# Arduino-Teensy-v5_PLUS_ESP-12E_4LAYER.net
KiCad netlist of a schematic drawn in EAGLE
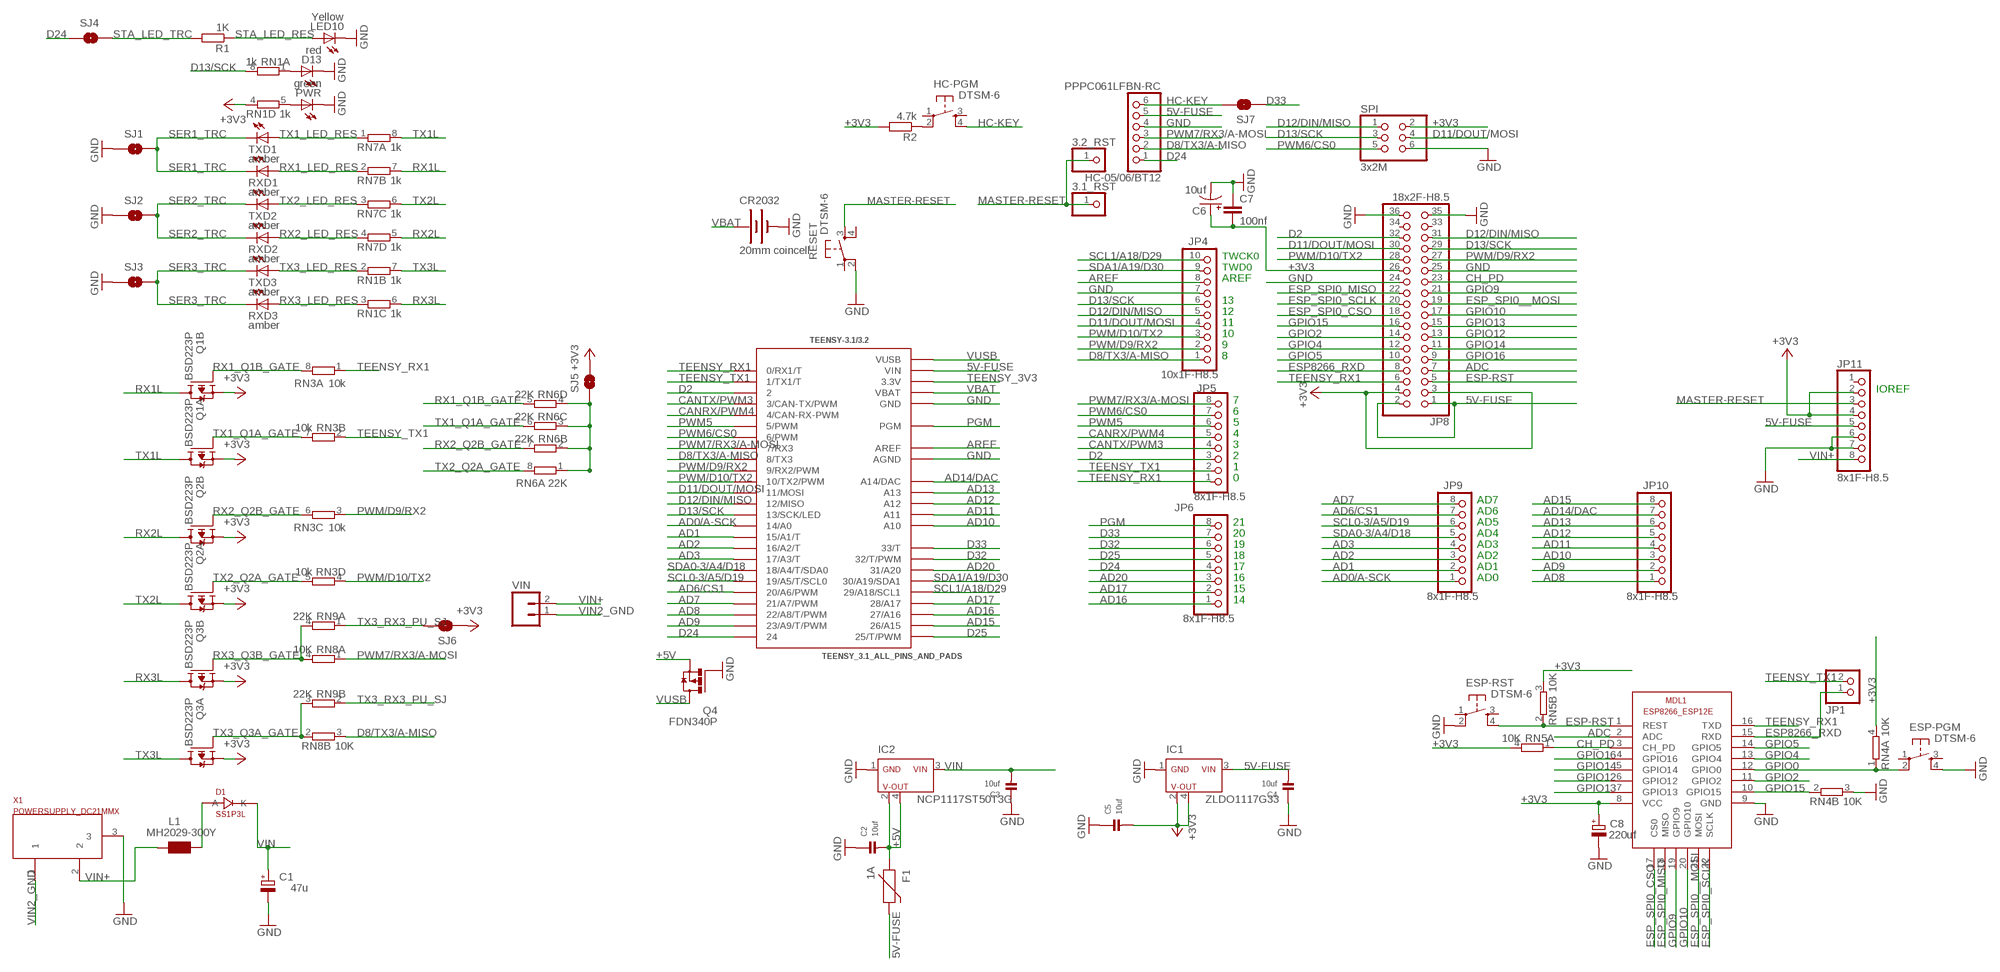
[diagram p0: schematic, sheet 1]

(export (version "E")
  (design (tool "Eeschema 10.0.6"))
  (components
    (comp (ref "3.1_RST")
      (value "PINHD-1X1CB")
      (footprint "eagle-import:1X01-CLEANBIG")
      (libsource (lib "eagle-import") (part "PINHD-1X1CB"))
    )
    (comp (ref "3.2_RST")
      (value "PINHD-1X1CB")
      (footprint "eagle-import:1X01-CLEANBIG")
      (libsource (lib "eagle-import") (part "PINHD-1X1CB"))
    )
    (comp (ref "C1")
      (value "47u")
      (footprint "eagle-import:PANASONIC_D")
      (libsource (lib "eagle-import") (part "CPOL-EUD"))
    )
    (comp (ref "C2")
      (value "10uf")
      (footprint "eagle-import:0805")
      (libsource (lib "eagle-import") (part "CAP_CERAMIC0805"))
    )
    (comp (ref "C3")
      (value "10uf")
      (footprint "eagle-import:0805")
      (libsource (lib "eagle-import") (part "CAP_CERAMIC0805"))
    )
    (comp (ref "C4")
      (value "10uf")
      (footprint "eagle-import:0805")
      (libsource (lib "eagle-import") (part "CAP_CERAMIC0805"))
    )
    (comp (ref "C5")
      (value "10uf")
      (footprint "eagle-import:0805")
      (libsource (lib "eagle-import") (part "CAP_CERAMIC0805"))
    )
    (comp (ref "C6")
      (value "10uf")
      (footprint "eagle-import:A_3216-18R")
      (libsource (lib "eagle-import") (part "CPOL-USA/3216-18R"))
    )
    (comp (ref "C7")
      (value "100nf")
      (footprint "eagle-import:C0603-ROUND")
      (libsource (lib "eagle-import") (part "C-EUC0603"))
    )
    (comp (ref "C8")
      (value "220uf")
      (footprint "eagle-import:SMC_B")
      (libsource (lib "eagle-import") (part "CPOL-EUSMCB"))
    )
    (comp (ref "CR2032")
      (value "20mm coincell")
      (footprint "eagle-import:BATTCON_20MM_4LEGS")
      (libsource (lib "eagle-import") (part "BATTERY20MM_4LEGS"))
    )
    (comp (ref "D1")
      (value "SS1P3L")
      (footprint "eagle-import:DO220AAL")
      (libsource (lib "eagle-import") (part "SS1P3L"))
    )
    (comp (ref "D13")
      (value "red")
      (footprint "eagle-import:CHIPLED_0805")
      (libsource (lib "eagle-import") (part "LEDCHIPLED_0805"))
    )
    (comp (ref "ESP-PGM")
      (value "DTSM-6")
      (footprint "eagle-import:DTSM-6")
      (libsource (lib "eagle-import") (part "DTSM-6"))
    )
    (comp (ref "ESP-RST")
      (value "DTSM-6")
      (footprint "eagle-import:DTSM-6")
      (libsource (lib "eagle-import") (part "DTSM-6"))
    )
    (comp (ref "F1")
      (value "1A")
      (footprint "eagle-import:PTC-1206")
      (libsource (lib "eagle-import") (part "PTCSMD"))
    )
    (comp (ref "HC-05/06/BT12")
      (value "PPPC061LFBN-RC")
      (footprint "eagle-import:1X06")
      (libsource (lib "eagle-import") (part "PINHD-1X6"))
    )
    (comp (ref "HC-PGM")
      (value "DTSM-6")
      (footprint "eagle-import:DTSM-6")
      (libsource (lib "eagle-import") (part "DTSM-6"))
    )
    (comp (ref "IC1")
      (value "ZLDO1117G33")
      (footprint "eagle-import:SOT223")
      (libsource (lib "eagle-import") (part "ZLDO1117G33"))
    )
    (comp (ref "IC2")
      (value "NCP1117ST50T3G")
      (footprint "eagle-import:SOT223")
      (libsource (lib "eagle-import") (part "NCP1117ST50T3G"))
    )
    (comp (ref "JP1")
      (value "PINHD-1X2")
      (footprint "eagle-import:1X02")
      (libsource (lib "eagle-import") (part "PINHD-1X2"))
    )
    (comp (ref "JP4")
      (value "10x1F-H8.5")
      (footprint "eagle-import:1X10")
      (libsource (lib "eagle-import") (part "PINHD-1X10"))
    )
    (comp (ref "JP5")
      (value "8x1F-H8.5")
      (footprint "eagle-import:1X08")
      (libsource (lib "eagle-import") (part "PINHD-1X8"))
    )
    (comp (ref "JP6")
      (value "8x1F-H8.5")
      (footprint "eagle-import:1X08")
      (libsource (lib "eagle-import") (part "PINHD-1X8"))
    )
    (comp (ref "JP8")
      (value "18x2F-H8.5")
      (footprint "eagle-import:2X18")
      (libsource (lib "eagle-import") (part "PINHD-2X18"))
    )
    (comp (ref "JP9")
      (value "8x1F-H8.5")
      (footprint "eagle-import:1X08")
      (libsource (lib "eagle-import") (part "PINHD-1X8"))
    )
    (comp (ref "JP10")
      (value "8x1F-H8.5")
      (footprint "eagle-import:1X08")
      (libsource (lib "eagle-import") (part "PINHD-1X8"))
    )
    (comp (ref "JP11")
      (value "8x1F-H8.5")
      (footprint "eagle-import:1X08")
      (libsource (lib "eagle-import") (part "PINHD-1X8"))
    )
    (comp (ref "L1")
      (value "MH2029-300Y")
      (footprint "eagle-import:0805")
      (libsource (lib "eagle-import") (part "WE-CBF_0805"))
    )
    (comp (ref "LED10")
      (value "Yellow")
      (footprint "eagle-import:CHIPLED_0805")
      (libsource (lib "eagle-import") (part "LEDCHIPLED_0805"))
    )
    (comp (ref "MDL1")
      (value "ESP8266-12E)")
      (footprint "eagle-import:ESP8266-ESP12E")
      (libsource (lib "eagle-import") (part "ESP8266-12EESP8266-ESP12E"))
    )
    (comp (ref "PWR")
      (value "green")
      (footprint "eagle-import:CHIPLED_0805")
      (libsource (lib "eagle-import") (part "LEDCHIPLED_0805"))
    )
    (comp (ref "Q1")
      (value "BSD223P")
      (footprint "eagle-import:SOT363_INFINEON")
      (libsource (lib "eagle-import") (part "BSD223P"))
    )
    (comp (ref "Q2")
      (value "BSD223P")
      (footprint "eagle-import:SOT363_INFINEON")
      (libsource (lib "eagle-import") (part "BSD223P"))
    )
    (comp (ref "Q3")
      (value "BSD223P")
      (footprint "eagle-import:SOT363_INFINEON")
      (libsource (lib "eagle-import") (part "BSD223P"))
    )
    (comp (ref "Q4")
      (value "FDN340P")
      (footprint "eagle-import:SUPER-SOT3")
      (libsource (lib "eagle-import") (part "FDN360P"))
    )
    (comp (ref "R1")
      (value "1K")
      (footprint "eagle-import:R0603")
      (libsource (lib "eagle-import") (part "R-EU_R0603"))
    )
    (comp (ref "R2")
      (value "4.7k")
      (footprint "eagle-import:R0603")
      (libsource (lib "eagle-import") (part "R-EU_R0603"))
    )
    (comp (ref "RESET")
      (value "DTSM-6")
      (footprint "eagle-import:DTSM-6")
      (libsource (lib "eagle-import") (part "DTSM-6"))
    )
    (comp (ref "RN1")
      (value "1k")
      (footprint "eagle-import:CAT16")
      (libsource (lib "eagle-import") (part "4R-NCAT16"))
    )
    (comp (ref "RN3")
      (value "10k")
      (footprint "eagle-import:CAT16")
      (libsource (lib "eagle-import") (part "4R-NCAT16"))
    )
    (comp (ref "RN4")
      (value "10K")
      (footprint "eagle-import:EXB34V")
      (libsource (lib "eagle-import") (part "2R-NEXB34V"))
    )
    (comp (ref "RN5")
      (value "10K")
      (footprint "eagle-import:EXB34V")
      (libsource (lib "eagle-import") (part "2R-NEXB34V"))
    )
    (comp (ref "RN6")
      (value "22K")
      (footprint "eagle-import:CAT16")
      (libsource (lib "eagle-import") (part "4R-NCAT16"))
    )
    (comp (ref "RN7")
      (value "1k")
      (footprint "eagle-import:CAT16")
      (libsource (lib "eagle-import") (part "4R-NCAT16"))
    )
    (comp (ref "RN8")
      (value "10K")
      (footprint "eagle-import:EXB34V")
      (libsource (lib "eagle-import") (part "2R-NEXB34V"))
    )
    (comp (ref "RN9")
      (value "22K")
      (footprint "eagle-import:EXB34V")
      (libsource (lib "eagle-import") (part "2R-NEXB34V"))
    )
    (comp (ref "RXD1")
      (value "amber")
      (footprint "eagle-import:CHIPLED_0805")
      (libsource (lib "eagle-import") (part "LEDCHIPLED_0805"))
    )
    (comp (ref "RXD2")
      (value "amber")
      (footprint "eagle-import:CHIPLED_0805")
      (libsource (lib "eagle-import") (part "LEDCHIPLED_0805"))
    )
    (comp (ref "RXD3")
      (value "amber")
      (footprint "eagle-import:CHIPLED_0805")
      (libsource (lib "eagle-import") (part "LEDCHIPLED_0805"))
    )
    (comp (ref "SJ1")
      (value "SOLDERJUMPERTRACE")
      (footprint "eagle-import:SJ_2S-TRACE")
      (libsource (lib "eagle-import") (part "SOLDERJUMPERTRACE"))
    )
    (comp (ref "SJ2")
      (value "SOLDERJUMPERTRACE")
      (footprint "eagle-import:SJ_2S-TRACE")
      (libsource (lib "eagle-import") (part "SOLDERJUMPERTRACE"))
    )
    (comp (ref "SJ3")
      (value "SOLDERJUMPERTRACE")
      (footprint "eagle-import:SJ_2S-TRACE")
      (libsource (lib "eagle-import") (part "SOLDERJUMPERTRACE"))
    )
    (comp (ref "SJ4")
      (value "SOLDERJUMPERTRACE")
      (footprint "eagle-import:SJ_2S-TRACE")
      (libsource (lib "eagle-import") (part "SOLDERJUMPERTRACE"))
    )
    (comp (ref "SJ5")
      (value "SOLDERJUMPERTRACE")
      (footprint "eagle-import:SJ_2S-TRACE")
      (libsource (lib "eagle-import") (part "SOLDERJUMPERTRACE"))
    )
    (comp (ref "SJ6")
      (value "SOLDERJUMPERTRACE")
      (footprint "eagle-import:SJ_2S-TRACE")
      (libsource (lib "eagle-import") (part "SOLDERJUMPERTRACE"))
    )
    (comp (ref "SJ7")
      (value "SOLDERJUMPERTRACE")
      (footprint "eagle-import:SJ_2S-TRACE")
      (libsource (lib "eagle-import") (part "SOLDERJUMPERTRACE"))
    )
    (comp (ref "SPI")
      (value "3x2M")
      (footprint "eagle-import:2X03")
      (libsource (lib "eagle-import") (part "PINHD-2X3"))
    )
    (comp (ref "TEENSY-3.1/3.2")
      (value "TEENSY_3.1_ALL_PINS_AND_PADS")
      (footprint "eagle-import:TEENSY3_ALL_PINS_&_PADS")
      (libsource (lib "eagle-import") (part "TEENSY_3.1_ALL_PINS_AND_PADS"))
    )
    (comp (ref "TXD1")
      (value "amber")
      (footprint "eagle-import:CHIPLED_0805")
      (libsource (lib "eagle-import") (part "LEDCHIPLED_0805"))
    )
    (comp (ref "TXD2")
      (value "amber")
      (footprint "eagle-import:CHIPLED_0805")
      (libsource (lib "eagle-import") (part "LEDCHIPLED_0805"))
    )
    (comp (ref "TXD3")
      (value "amber")
      (footprint "eagle-import:CHIPLED_0805")
      (libsource (lib "eagle-import") (part "LEDCHIPLED_0805"))
    )
    (comp (ref "VIN")
      (value "M02LOCK_LONGPADS")
      (footprint "eagle-import:1X02_LOCK_LONGPADS")
      (libsource (lib "eagle-import") (part "M02LOCK_LONGPADS"))
    )
    (comp (ref "X1")
      (value "POWERSUPPLY_DC21MMX")
      (footprint "eagle-import:POWERSUPPLY_DC-21MM")
      (libsource (lib "eagle-import") (part "POWERSUPPLY_DC21MMX"))
    )
  )
  (nets
    (net (code "1") (name "+3V3") (class "Default")
      (node (ref "C5") (pin "2") (pinfunction "P$2_2") (pintype "passive"))
      (node (ref "C6") (pin "+") (pinfunction "+_+") (pintype "passive"))
      (node (ref "C7") (pin "2") (pinfunction "2_2") (pintype "passive"))
      (node (ref "C8") (pin "+") (pinfunction "+_+") (pintype "passive"))
      (node (ref "IC1") (pin "2") (pinfunction "VOUT_2") (pintype "output"))
      (node (ref "IC1") (pin "4") (pinfunction "VOUT_4") (pintype "power_in"))
      (node (ref "JP11") (pin "2") (pinfunction "2_2") (pintype "passive"))
      (node (ref "JP11") (pin "4") (pinfunction "4_4") (pintype "passive"))
      (node (ref "JP8") (pin "26") (pinfunction "26_26") (pintype "passive"))
      (node (ref "JP8") (pin "3") (pinfunction "3_3") (pintype "passive"))
      (node (ref "JP8") (pin "4") (pinfunction "4_4") (pintype "passive"))
      (node (ref "MDL1") (pin "8") (pinfunction "VCC_8") (pintype "bidirectional"))
      (node (ref "Q1") (pin "1") (pinfunction "S_1") (pintype "passive"))
      (node (ref "Q1") (pin "4") (pinfunction "S_4") (pintype "passive"))
      (node (ref "Q2") (pin "1") (pinfunction "S_1") (pintype "passive"))
      (node (ref "Q2") (pin "4") (pinfunction "S_4") (pintype "passive"))
      (node (ref "Q3") (pin "1") (pinfunction "S_1") (pintype "passive"))
      (node (ref "Q3") (pin "4") (pinfunction "S_4") (pintype "passive"))
      (node (ref "R2") (pin "2") (pinfunction "2_2") (pintype "passive"))
      (node (ref "RN1") (pin "4") (pinfunction "1_4") (pintype "passive"))
      (node (ref "RN4") (pin "4") (pinfunction "2_4") (pintype "passive"))
      (node (ref "RN5") (pin "3") (pinfunction "2_3") (pintype "passive"))
      (node (ref "RN5") (pin "4") (pinfunction "2_4") (pintype "passive"))
      (node (ref "SJ5") (pin "2") (pinfunction "2_2") (pintype "passive"))
      (node (ref "SJ6") (pin "1") (pinfunction "1_1") (pintype "passive"))
      (node (ref "SPI") (pin "2") (pinfunction "2_2") (pintype "passive"))
    )
    (net (code "2") (name "/+5V") (class "Default")
      (node (ref "C2") (pin "2") (pinfunction "P$2_2") (pintype "passive"))
      (node (ref "F1") (pin "1") (pinfunction "1_1") (pintype "bidirectional"))
      (node (ref "IC2") (pin "2") (pinfunction "VOUT_2") (pintype "output"))
      (node (ref "IC2") (pin "4") (pinfunction "VOUT_4") (pintype "power_in"))
      (node (ref "Q4") (pin "2") (pinfunction "S_2") (pintype "passive"))
    )
    (net (code "3") (name "/5V-FUSE") (class "Default")
      (node (ref "C4") (pin "2") (pinfunction "P$2_2") (pintype "passive"))
      (node (ref "F1") (pin "2") (pinfunction "2_2") (pintype "bidirectional"))
      (node (ref "HC-05/06/BT12") (pin "5") (pinfunction "5_5") (pintype "passive"))
      (node (ref "IC1") (pin "3") (pinfunction "VIN_3") (pintype "power_in"))
      (node (ref "JP11") (pin "5") (pinfunction "5_5") (pintype "passive"))
      (node (ref "JP8") (pin "1") (pinfunction "1_1") (pintype "passive"))
      (node (ref "JP8") (pin "2") (pinfunction "2_2") (pintype "passive"))
      (node (ref "TEENSY-3.1/3.2") (pin "VIN") (pinfunction "VIN_VIN") (pintype "power_in"))
    )
    (net (code "4") (name "/AD0{slash}A-SCK") (class "Default")
      (node (ref "JP9") (pin "1") (pinfunction "1_1") (pintype "passive"))
      (node (ref "TEENSY-3.1/3.2") (pin "14/A0") (pinfunction "14/A0_14/A0") (pintype "bidirectional"))
    )
    (net (code "5") (name "/AD1") (class "Default")
      (node (ref "JP9") (pin "2") (pinfunction "2_2") (pintype "passive"))
      (node (ref "TEENSY-3.1/3.2") (pin "15/A1") (pinfunction "15/A1/T_15/A1") (pintype "bidirectional"))
    )
    (net (code "6") (name "/AD2") (class "Default")
      (node (ref "JP9") (pin "3") (pinfunction "3_3") (pintype "passive"))
      (node (ref "TEENSY-3.1/3.2") (pin "16/A2") (pinfunction "16/A2/T_16/A2") (pintype "bidirectional"))
    )
    (net (code "7") (name "/AD3") (class "Default")
      (node (ref "JP9") (pin "4") (pinfunction "4_4") (pintype "passive"))
      (node (ref "TEENSY-3.1/3.2") (pin "17/A3") (pinfunction "17/A3/T_17/A3") (pintype "bidirectional"))
    )
    (net (code "8") (name "/AD6{slash}CS1") (class "Default")
      (node (ref "JP9") (pin "7") (pinfunction "7_7") (pintype "passive"))
      (node (ref "TEENSY-3.1/3.2") (pin "20/A6") (pinfunction "20/A6/PWM_20/A6") (pintype "bidirectional"))
    )
    (net (code "9") (name "/AD7") (class "Default")
      (node (ref "JP9") (pin "8") (pinfunction "8_8") (pintype "passive"))
      (node (ref "TEENSY-3.1/3.2") (pin "21/A7") (pinfunction "21/A7/PWM_21/A7") (pintype "bidirectional"))
    )
    (net (code "10") (name "/AD8") (class "Default")
      (node (ref "JP10") (pin "1") (pinfunction "1_1") (pintype "passive"))
      (node (ref "TEENSY-3.1/3.2") (pin "22/A8") (pinfunction "22/A8/T/PWM_22/A8") (pintype "bidirectional"))
    )
    (net (code "11") (name "/AD9") (class "Default")
      (node (ref "JP10") (pin "2") (pinfunction "2_2") (pintype "passive"))
      (node (ref "TEENSY-3.1/3.2") (pin "23/A9") (pinfunction "23/A9/T/PWM_23/A9") (pintype "bidirectional"))
    )
    (net (code "12") (name "/AD10") (class "Default")
      (node (ref "JP10") (pin "3") (pinfunction "3_3") (pintype "passive"))
      (node (ref "TEENSY-3.1/3.2") (pin "A10") (pinfunction "A10_A10") (pintype "bidirectional"))
    )
    (net (code "13") (name "/AD11") (class "Default")
      (node (ref "JP10") (pin "4") (pinfunction "4_4") (pintype "passive"))
      (node (ref "TEENSY-3.1/3.2") (pin "A11") (pinfunction "A11_A11") (pintype "bidirectional"))
    )
    (net (code "14") (name "/AD12") (class "Default")
      (node (ref "JP10") (pin "5") (pinfunction "5_5") (pintype "passive"))
      (node (ref "TEENSY-3.1/3.2") (pin "A12") (pinfunction "A12_A12") (pintype "bidirectional"))
    )
    (net (code "15") (name "/AD13") (class "Default")
      (node (ref "JP10") (pin "6") (pinfunction "6_6") (pintype "passive"))
      (node (ref "TEENSY-3.1/3.2") (pin "A13") (pinfunction "A13_A13") (pintype "bidirectional"))
    )
    (net (code "16") (name "/AD14{slash}DAC") (class "Default")
      (node (ref "JP10") (pin "7") (pinfunction "7_7") (pintype "passive"))
      (node (ref "TEENSY-3.1/3.2") (pin "RESET/DAC") (pinfunction "A14/DAC_RESET/DAC") (pintype "bidirectional"))
    )
    (net (code "17") (name "/AD15") (class "Default")
      (node (ref "JP10") (pin "8") (pinfunction "8_8") (pintype "passive"))
      (node (ref "TEENSY-3.1/3.2") (pin "26") (pinfunction "26/A15_26") (pintype "bidirectional"))
    )
    (net (code "18") (name "/AD16") (class "Default")
      (node (ref "JP6") (pin "1") (pinfunction "1_1") (pintype "passive"))
      (node (ref "TEENSY-3.1/3.2") (pin "27") (pinfunction "27/A16_27") (pintype "bidirectional"))
    )
    (net (code "19") (name "/AD17") (class "Default")
      (node (ref "JP6") (pin "2") (pinfunction "2_2") (pintype "passive"))
      (node (ref "TEENSY-3.1/3.2") (pin "28") (pinfunction "28/A17_28") (pintype "bidirectional"))
    )
    (net (code "20") (name "/AD20") (class "Default")
      (node (ref "JP6") (pin "3") (pinfunction "3_3") (pintype "passive"))
      (node (ref "TEENSY-3.1/3.2") (pin "31") (pinfunction "31/A20_31") (pintype "bidirectional"))
    )
    (net (code "21") (name "/ADC") (class "Default")
      (node (ref "JP8") (pin "7") (pinfunction "7_7") (pintype "passive"))
      (node (ref "MDL1") (pin "2") (pinfunction "ADC_2") (pintype "bidirectional"))
    )
    (net (code "22") (name "/AREF") (class "Default")
      (node (ref "JP4") (pin "8") (pinfunction "8_8") (pintype "passive"))
      (node (ref "TEENSY-3.1/3.2") (pin "AREF") (pinfunction "AREF_AREF") (pintype "power_in"))
    )
    (net (code "23") (name "/CANRX{slash}PWM4") (class "Default")
      (node (ref "JP5") (pin "5") (pinfunction "5_5") (pintype "passive"))
      (node (ref "TEENSY-3.1/3.2") (pin "4") (pinfunction "4/CAN-RX-PWM_4") (pintype "bidirectional"))
    )
    (net (code "24") (name "/CANTX{slash}PWM3") (class "Default")
      (node (ref "JP5") (pin "4") (pinfunction "4_4") (pintype "passive"))
      (node (ref "TEENSY-3.1/3.2") (pin "3") (pinfunction "3/CAN-TX/PWM_3") (pintype "bidirectional"))
    )
    (net (code "25") (name "/CH_PD") (class "Default")
      (node (ref "JP8") (pin "23") (pinfunction "23_23") (pintype "passive"))
      (node (ref "MDL1") (pin "3") (pinfunction "CH_PD_3") (pintype "bidirectional"))
      (node (ref "RN5") (pin "1") (pinfunction "1_1") (pintype "passive"))
    )
    (net (code "26") (name "/D2") (class "Default")
      (node (ref "JP5") (pin "3") (pinfunction "3_3") (pintype "passive"))
      (node (ref "JP8") (pin "32") (pinfunction "32_32") (pintype "passive"))
      (node (ref "TEENSY-3.1/3.2") (pin "2") (pinfunction "2_2") (pintype "bidirectional"))
    )
    (net (code "27") (name "/D8{slash}TX3{slash}A-MISO") (class "Default")
      (node (ref "HC-05/06/BT12") (pin "2") (pinfunction "2_2") (pintype "passive"))
      (node (ref "JP4") (pin "1") (pinfunction "1_1") (pintype "passive"))
      (node (ref "RN8") (pin "3") (pinfunction "2_3") (pintype "passive"))
      (node (ref "TEENSY-3.1/3.2") (pin "8") (pinfunction "8/TX3_8") (pintype "bidirectional"))
    )
    (net (code "28") (name "/D11{slash}DOUT{slash}MOSI") (class "Default")
      (node (ref "JP4") (pin "4") (pinfunction "4_4") (pintype "passive"))
      (node (ref "JP8") (pin "30") (pinfunction "30_30") (pintype "passive"))
      (node (ref "SPI") (pin "4") (pinfunction "4_4") (pintype "passive"))
      (node (ref "TEENSY-3.1/3.2") (pin "11") (pinfunction "11/MOSI_11") (pintype "bidirectional"))
    )
    (net (code "29") (name "/D12{slash}DIN{slash}MISO") (class "Default")
      (node (ref "JP4") (pin "5") (pinfunction "5_5") (pintype "passive"))
      (node (ref "JP8") (pin "31") (pinfunction "31_31") (pintype "passive"))
      (node (ref "SPI") (pin "1") (pinfunction "1_1") (pintype "passive"))
      (node (ref "TEENSY-3.1/3.2") (pin "12") (pinfunction "12/MISO_12") (pintype "bidirectional"))
    )
    (net (code "30") (name "/D13{slash}SCK") (class "Default")
      (node (ref "JP4") (pin "6") (pinfunction "6_6") (pintype "passive"))
      (node (ref "JP8") (pin "29") (pinfunction "29_29") (pintype "passive"))
      (node (ref "RN1") (pin "8") (pinfunction "2_8") (pintype "passive"))
      (node (ref "SPI") (pin "3") (pinfunction "3_3") (pintype "passive"))
      (node (ref "TEENSY-3.1/3.2") (pin "13") (pinfunction "13/SCK/LED_13") (pintype "bidirectional"))
    )
    (net (code "31") (name "/D24") (class "Default")
      (node (ref "HC-05/06/BT12") (pin "1") (pinfunction "1_1") (pintype "passive"))
      (node (ref "JP6") (pin "4") (pinfunction "4_4") (pintype "passive"))
      (node (ref "SJ4") (pin "1") (pinfunction "1_1") (pintype "passive"))
      (node (ref "TEENSY-3.1/3.2") (pin "24") (pinfunction "24_24") (pintype "bidirectional"))
    )
    (net (code "32") (name "/D25") (class "Default")
      (node (ref "JP6") (pin "5") (pinfunction "5_5") (pintype "passive"))
      (node (ref "TEENSY-3.1/3.2") (pin "25") (pinfunction "25/T/PWM_25") (pintype "bidirectional"))
    )
    (net (code "33") (name "/D32") (class "Default")
      (node (ref "JP6") (pin "6") (pinfunction "6_6") (pintype "passive"))
      (node (ref "TEENSY-3.1/3.2") (pin "32") (pinfunction "32/T/PWM_32") (pintype "bidirectional"))
    )
    (net (code "34") (name "/D33") (class "Default")
      (node (ref "JP6") (pin "7") (pinfunction "7_7") (pintype "passive"))
      (node (ref "SJ7") (pin "2") (pinfunction "2_2") (pintype "passive"))
      (node (ref "TEENSY-3.1/3.2") (pin "33") (pinfunction "33/T_33") (pintype "bidirectional"))
    )
    (net (code "35") (name "/ESP-RST") (class "Default")
      (node (ref "ESP-RST") (pin "4") (pinfunction "4_4") (pintype "passive"))
      (node (ref "JP8") (pin "5") (pinfunction "5_5") (pintype "passive"))
      (node (ref "MDL1") (pin "1") (pinfunction "REST_1") (pintype "bidirectional"))
      (node (ref "RN5") (pin "2") (pinfunction "1_2") (pintype "passive"))
    )
    (net (code "36") (name "/ESP8266_RXD") (class "Default")
      (node (ref "JP1") (pin "1") (pinfunction "1_1") (pintype "passive"))
      (node (ref "JP8") (pin "8") (pinfunction "8_8") (pintype "passive"))
      (node (ref "MDL1") (pin "15") (pinfunction "RXD_15") (pintype "bidirectional"))
    )
    (net (code "37") (name "/ESP_SPI0_CSO") (class "Default")
      (node (ref "JP8") (pin "18") (pinfunction "18_18") (pintype "passive"))
      (node (ref "MDL1") (pin "17") (pinfunction "CS0_17") (pintype "bidirectional"))
    )
    (net (code "38") (name "/ESP_SPI0_MISO") (class "Default")
      (node (ref "JP8") (pin "22") (pinfunction "22_22") (pintype "passive"))
      (node (ref "MDL1") (pin "18") (pinfunction "MISO_18") (pintype "bidirectional"))
    )
    (net (code "39") (name "/ESP_SPI0_SCLK") (class "Default")
      (node (ref "JP8") (pin "20") (pinfunction "20_20") (pintype "passive"))
      (node (ref "MDL1") (pin "22") (pinfunction "SCLK_22") (pintype "bidirectional"))
    )
    (net (code "40") (name "/ESP_SPI0__MOSI") (class "Default")
      (node (ref "JP8") (pin "19") (pinfunction "19_19") (pintype "passive"))
      (node (ref "MDL1") (pin "21") (pinfunction "MOSI_21") (pintype "bidirectional"))
    )
    (net (code "41") (name "/GPIO0") (class "Default")
      (node (ref "ESP-PGM") (pin "2") (pinfunction "2_2") (pintype "passive"))
      (node (ref "MDL1") (pin "12") (pinfunction "GPIO0_12") (pintype "bidirectional"))
      (node (ref "RN4") (pin "1") (pinfunction "1_1") (pintype "passive"))
    )
    (net (code "42") (name "/GPIO2") (class "Default")
      (node (ref "JP8") (pin "14") (pinfunction "14_14") (pintype "passive"))
      (node (ref "MDL1") (pin "11") (pinfunction "GPIO2_11") (pintype "bidirectional"))
    )
    (net (code "43") (name "/GPIO4") (class "Default")
      (node (ref "JP8") (pin "12") (pinfunction "12_12") (pintype "passive"))
      (node (ref "MDL1") (pin "13") (pinfunction "GPIO4_13") (pintype "bidirectional"))
    )
    (net (code "44") (name "/GPIO5") (class "Default")
      (node (ref "JP8") (pin "10") (pinfunction "10_10") (pintype "passive"))
      (node (ref "MDL1") (pin "14") (pinfunction "GPIO5_14") (pintype "bidirectional"))
    )
    (net (code "45") (name "/GPIO9") (class "Default")
      (node (ref "JP8") (pin "21") (pinfunction "21_21") (pintype "passive"))
      (node (ref "MDL1") (pin "19") (pinfunction "GPIO9_19") (pintype "bidirectional"))
    )
    (net (code "46") (name "/GPIO10") (class "Default")
      (node (ref "JP8") (pin "17") (pinfunction "17_17") (pintype "passive"))
      (node (ref "MDL1") (pin "20") (pinfunction "GPIO10_20") (pintype "bidirectional"))
    )
    (net (code "47") (name "/GPIO12") (class "Default")
      (node (ref "JP8") (pin "13") (pinfunction "13_13") (pintype "passive"))
      (node (ref "MDL1") (pin "6") (pinfunction "GPIO12_6") (pintype "bidirectional"))
    )
    (net (code "48") (name "/GPIO13") (class "Default")
      (node (ref "JP8") (pin "15") (pinfunction "15_15") (pintype "passive"))
      (node (ref "MDL1") (pin "7") (pinfunction "GPIO13_7") (pintype "bidirectional"))
    )
    (net (code "49") (name "/GPIO14") (class "Default")
      (node (ref "JP8") (pin "11") (pinfunction "11_11") (pintype "passive"))
      (node (ref "MDL1") (pin "5") (pinfunction "GPIO14_5") (pintype "bidirectional"))
    )
    (net (code "50") (name "/GPIO15") (class "Default")
      (node (ref "JP8") (pin "16") (pinfunction "16_16") (pintype "passive"))
      (node (ref "MDL1") (pin "10") (pinfunction "GPIO15_10") (pintype "bidirectional"))
      (node (ref "RN4") (pin "2") (pinfunction "1_2") (pintype "passive"))
    )
    (net (code "51") (name "/GPIO16") (class "Default")
      (node (ref "JP8") (pin "9") (pinfunction "9_9") (pintype "passive"))
      (node (ref "MDL1") (pin "4") (pinfunction "GPIO16_4") (pintype "bidirectional"))
    )
    (net (code "52") (name "/HC-KEY") (class "Default")
      (node (ref "HC-05/06/BT12") (pin "6") (pinfunction "6_6") (pintype "passive"))
      (node (ref "HC-PGM") (pin "4") (pinfunction "4_4") (pintype "passive"))
      (node (ref "SJ7") (pin "1") (pinfunction "1_1") (pintype "passive"))
    )
    (net (code "53") (name "/MASTER-RESET") (class "Default")
      (node (ref "3.1_RST") (pin "1") (pinfunction "1_1") (pintype "passive"))
      (node (ref "3.2_RST") (pin "1") (pinfunction "1_1") (pintype "passive"))
      (node (ref "JP11") (pin "3") (pinfunction "3_3") (pintype "passive"))
      (node (ref "RESET") (pin "3") (pinfunction "3_3") (pintype "passive"))
    )
    (net (code "54") (name "/PGM") (class "Default")
      (node (ref "JP6") (pin "8") (pinfunction "8_8") (pintype "passive"))
      (node (ref "TEENSY-3.1/3.2") (pin "PGM") (pinfunction "PGM_PGM") (pintype "bidirectional"))
    )
    (net (code "55") (name "/PWM5") (class "Default")
      (node (ref "JP5") (pin "6") (pinfunction "6_6") (pintype "passive"))
      (node (ref "TEENSY-3.1/3.2") (pin "5") (pinfunction "5/PWM_5") (pintype "bidirectional"))
    )
    (net (code "56") (name "/PWM6{slash}CS0") (class "Default")
      (node (ref "JP5") (pin "7") (pinfunction "7_7") (pintype "passive"))
      (node (ref "SPI") (pin "5") (pinfunction "5_5") (pintype "passive"))
      (node (ref "TEENSY-3.1/3.2") (pin "6") (pinfunction "6/PWM_6") (pintype "bidirectional"))
    )
    (net (code "57") (name "/PWM7{slash}RX3{slash}A-MOSI") (class "Default")
      (node (ref "HC-05/06/BT12") (pin "3") (pinfunction "3_3") (pintype "passive"))
      (node (ref "JP5") (pin "8") (pinfunction "8_8") (pintype "passive"))
      (node (ref "RN8") (pin "1") (pinfunction "1_1") (pintype "passive"))
      (node (ref "TEENSY-3.1/3.2") (pin "7") (pinfunction "7/RX3_7") (pintype "bidirectional"))
    )
    (net (code "58") (name "/PWM{slash}D9{slash}RX2") (class "Default")
      (node (ref "JP4") (pin "2") (pinfunction "2_2") (pintype "passive"))
      (node (ref "JP8") (pin "27") (pinfunction "27_27") (pintype "passive"))
      (node (ref "RN3") (pin "3") (pinfunction "1_3") (pintype "passive"))
      (node (ref "TEENSY-3.1/3.2") (pin "9") (pinfunction "9/RX2/PWM_9") (pintype "bidirectional"))
    )
    (net (code "59") (name "/PWM{slash}D10{slash}TX2") (class "Default")
      (node (ref "JP4") (pin "3") (pinfunction "3_3") (pintype "passive"))
      (node (ref "JP8") (pin "28") (pinfunction "28_28") (pintype "passive"))
      (node (ref "RN3") (pin "4") (pinfunction "1_4") (pintype "passive"))
      (node (ref "TEENSY-3.1/3.2") (pin "10") (pinfunction "10/TX2/PWM_10") (pintype "bidirectional"))
    )
    (net (code "60") (name "/RX1L") (class "Default")
      (node (ref "Q1") (pin "3") (pinfunction "D_3") (pintype "passive"))
      (node (ref "RN7") (pin "7") (pinfunction "2_7") (pintype "passive"))
    )
    (net (code "61") (name "/RX1_LED_RES") (class "Default")
      (node (ref "RN7") (pin "2") (pinfunction "1_2") (pintype "passive"))
      (node (ref "RXD1") (pin "A") (pinfunction "A_A") (pintype "passive"))
    )
    (net (code "62") (name "/RX1_Q1B_GATE") (class "Default")
      (node (ref "Q1") (pin "5") (pinfunction "G_5") (pintype "passive"))
      (node (ref "RN3") (pin "8") (pinfunction "2_8") (pintype "passive"))
      (node (ref "RN6") (pin "5") (pinfunction "2_5") (pintype "passive"))
    )
    (net (code "63") (name "/RX2L") (class "Default")
      (node (ref "Q2") (pin "3") (pinfunction "D_3") (pintype "passive"))
      (node (ref "RN7") (pin "5") (pinfunction "2_5") (pintype "passive"))
    )
    (net (code "64") (name "/RX2_LED_RES") (class "Default")
      (node (ref "RN7") (pin "4") (pinfunction "1_4") (pintype "passive"))
      (node (ref "RXD2") (pin "A") (pinfunction "A_A") (pintype "passive"))
    )
    (net (code "65") (name "/RX2_Q2B_GATE") (class "Default")
      (node (ref "Q2") (pin "5") (pinfunction "G_5") (pintype "passive"))
      (node (ref "RN3") (pin "6") (pinfunction "2_6") (pintype "passive"))
      (node (ref "RN6") (pin "7") (pinfunction "2_7") (pintype "passive"))
    )
    (net (code "66") (name "/RX3L") (class "Default")
      (node (ref "Q3") (pin "3") (pinfunction "D_3") (pintype "passive"))
      (node (ref "RN1") (pin "6") (pinfunction "2_6") (pintype "passive"))
    )
    (net (code "67") (name "/RX3_LED_RES") (class "Default")
      (node (ref "RN1") (pin "3") (pinfunction "1_3") (pintype "passive"))
      (node (ref "RXD3") (pin "A") (pinfunction "A_A") (pintype "passive"))
    )
    (net (code "68") (name "/RX3_Q3B_GATE") (class "Default")
      (node (ref "Q3") (pin "5") (pinfunction "G_5") (pintype "passive"))
      (node (ref "RN8") (pin "4") (pinfunction "2_4") (pintype "passive"))
      (node (ref "RN9") (pin "4") (pinfunction "2_4") (pintype "passive"))
    )
    (net (code "69") (name "/SCL0-3{slash}A5{slash}D19") (class "Default")
      (node (ref "JP9") (pin "6") (pinfunction "6_6") (pintype "passive"))
      (node (ref "TEENSY-3.1/3.2") (pin "19/A5") (pinfunction "19/A5/T/SCL0_19/A5") (pintype "bidirectional"))
    )
    (net (code "70") (name "/SCL1{slash}A18{slash}D29") (class "Default")
      (node (ref "JP4") (pin "10") (pinfunction "10_10") (pintype "passive"))
      (node (ref "TEENSY-3.1/3.2") (pin "29") (pinfunction "29/A18/SCL1_29") (pintype "bidirectional"))
    )
    (net (code "71") (name "/SDA0-3{slash}A4{slash}D18") (class "Default")
      (node (ref "JP9") (pin "5") (pinfunction "5_5") (pintype "passive"))
      (node (ref "TEENSY-3.1/3.2") (pin "18/A4") (pinfunction "18/A4/T/SDA0_18/A4") (pintype "bidirectional"))
    )
    (net (code "72") (name "/SDA1{slash}A19{slash}D30") (class "Default")
      (node (ref "JP4") (pin "9") (pinfunction "9_9") (pintype "passive"))
      (node (ref "TEENSY-3.1/3.2") (pin "30") (pinfunction "30/A19/SDA1_30") (pintype "bidirectional"))
    )
    (net (code "73") (name "/SER1_TRC") (class "Default")
      (node (ref "RXD1") (pin "C") (pinfunction "C_C") (pintype "passive"))
      (node (ref "SJ1") (pin "2") (pinfunction "2_2") (pintype "passive"))
      (node (ref "TXD1") (pin "C") (pinfunction "C_C") (pintype "passive"))
    )
    (net (code "74") (name "/SER2_TRC") (class "Default")
      (node (ref "RXD2") (pin "C") (pinfunction "C_C") (pintype "passive"))
      (node (ref "SJ2") (pin "2") (pinfunction "2_2") (pintype "passive"))
      (node (ref "TXD2") (pin "C") (pinfunction "C_C") (pintype "passive"))
    )
    (net (code "75") (name "/SER3_TRC") (class "Default")
      (node (ref "RXD3") (pin "C") (pinfunction "C_C") (pintype "passive"))
      (node (ref "SJ3") (pin "2") (pinfunction "2_2") (pintype "passive"))
      (node (ref "TXD3") (pin "C") (pinfunction "C_C") (pintype "passive"))
    )
    (net (code "76") (name "/STA_LED_RES") (class "Default")
      (node (ref "LED10") (pin "A") (pinfunction "A_A") (pintype "passive"))
      (node (ref "R1") (pin "1") (pinfunction "1_1") (pintype "passive"))
    )
    (net (code "77") (name "/STA_LED_TRC") (class "Default")
      (node (ref "R1") (pin "2") (pinfunction "2_2") (pintype "passive"))
      (node (ref "SJ4") (pin "2") (pinfunction "2_2") (pintype "passive"))
    )
    (net (code "78") (name "/TEENSY_3V3") (class "Default")
      (node (ref "TEENSY-3.1/3.2") (pin "3.3V") (pinfunction "3.3V_3.3V") (pintype "power_in"))
      (node (ref "TEENSY-3.1/3.2") (pin "3.3V1") (pinfunction "3.3V_3.3V1") (pintype "power_in"))
      (node (ref "TEENSY-3.1/3.2") (pin "3.3V2") (pinfunction "3.3V_3.3V2") (pintype "power_in"))
    )
    (net (code "79") (name "/TEENSY_RX1") (class "Default")
      (node (ref "JP5") (pin "1") (pinfunction "1_1") (pintype "passive"))
      (node (ref "JP8") (pin "6") (pinfunction "6_6") (pintype "passive"))
      (node (ref "MDL1") (pin "16") (pinfunction "TXD_16") (pintype "bidirectional"))
      (node (ref "RN3") (pin "1") (pinfunction "1_1") (pintype "passive"))
      (node (ref "TEENSY-3.1/3.2") (pin "0") (pinfunction "0/RX1/T_0") (pintype "bidirectional"))
    )
    (net (code "80") (name "/TEENSY_TX1") (class "Default")
      (node (ref "JP1") (pin "2") (pinfunction "2_2") (pintype "passive"))
      (node (ref "JP5") (pin "2") (pinfunction "2_2") (pintype "passive"))
      (node (ref "RN3") (pin "2") (pinfunction "1_2") (pintype "passive"))
      (node (ref "TEENSY-3.1/3.2") (pin "1") (pinfunction "1/TX1/T_1") (pintype "bidirectional"))
    )
    (net (code "81") (name "/TX1L") (class "Default")
      (node (ref "Q1") (pin "6") (pinfunction "D_6") (pintype "passive"))
      (node (ref "RN7") (pin "8") (pinfunction "2_8") (pintype "passive"))
    )
    (net (code "82") (name "/TX1_LED_RES") (class "Default")
      (node (ref "RN7") (pin "1") (pinfunction "1_1") (pintype "passive"))
      (node (ref "TXD1") (pin "A") (pinfunction "A_A") (pintype "passive"))
    )
    (net (code "83") (name "/TX1_Q1A_GATE") (class "Default")
      (node (ref "Q1") (pin "2") (pinfunction "G_2") (pintype "passive"))
      (node (ref "RN3") (pin "7") (pinfunction "2_7") (pintype "passive"))
      (node (ref "RN6") (pin "6") (pinfunction "2_6") (pintype "passive"))
    )
    (net (code "84") (name "/TX2L") (class "Default")
      (node (ref "Q2") (pin "6") (pinfunction "D_6") (pintype "passive"))
      (node (ref "RN7") (pin "6") (pinfunction "2_6") (pintype "passive"))
    )
    (net (code "85") (name "/TX2_LED_RES") (class "Default")
      (node (ref "RN7") (pin "3") (pinfunction "1_3") (pintype "passive"))
      (node (ref "TXD2") (pin "A") (pinfunction "A_A") (pintype "passive"))
    )
    (net (code "86") (name "/TX2_Q2A_GATE") (class "Default")
      (node (ref "Q2") (pin "2") (pinfunction "G_2") (pintype "passive"))
      (node (ref "RN3") (pin "5") (pinfunction "2_5") (pintype "passive"))
      (node (ref "RN6") (pin "8") (pinfunction "2_8") (pintype "passive"))
    )
    (net (code "87") (name "/TX3L") (class "Default")
      (node (ref "Q3") (pin "6") (pinfunction "D_6") (pintype "passive"))
      (node (ref "RN1") (pin "7") (pinfunction "2_7") (pintype "passive"))
    )
    (net (code "88") (name "/TX3_LED_RES") (class "Default")
      (node (ref "RN1") (pin "2") (pinfunction "1_2") (pintype "passive"))
      (node (ref "TXD3") (pin "A") (pinfunction "A_A") (pintype "passive"))
    )
    (net (code "89") (name "/TX3_Q3A_GATE") (class "Default")
      (node (ref "Q3") (pin "2") (pinfunction "G_2") (pintype "passive"))
      (node (ref "RN8") (pin "2") (pinfunction "1_2") (pintype "passive"))
      (node (ref "RN9") (pin "3") (pinfunction "2_3") (pintype "passive"))
    )
    (net (code "90") (name "/TX3_RX3_PU_SJ") (class "Default")
      (node (ref "RN9") (pin "1") (pinfunction "1_1") (pintype "passive"))
      (node (ref "RN9") (pin "2") (pinfunction "1_2") (pintype "passive"))
      (node (ref "SJ6") (pin "2") (pinfunction "2_2") (pintype "passive"))
    )
    (net (code "91") (name "/VBAT") (class "Default")
      (node (ref "CR2032") (pin "POSITIVE@1") (pinfunction "+_POSITIVE@1") (pintype "power_in"))
      (node (ref "CR2032") (pin "POSITIVE@2") (pinfunction "+_POSITIVE@2") (pintype "power_in"))
      (node (ref "CR2032") (pin "POSITIVE@3") (pinfunction "+_POSITIVE@3") (pintype "power_in"))
      (node (ref "CR2032") (pin "POSITIVE@4") (pinfunction "+_POSITIVE@4") (pintype "power_in"))
      (node (ref "TEENSY-3.1/3.2") (pin "VBAT") (pinfunction "VBAT_VBAT") (pintype "power_in"))
    )
    (net (code "92") (name "/VIN") (class "Default")
      (node (ref "C1") (pin "+") (pinfunction "+_+") (pintype "passive"))
      (node (ref "C3") (pin "2") (pinfunction "P$2_2") (pintype "passive"))
      (node (ref "D1") (pin "P$1") (pinfunction "K_P$1") (pintype "bidirectional"))
      (node (ref "IC2") (pin "3") (pinfunction "VIN_3") (pintype "power_in"))
    )
    (net (code "93") (name "/VIN+") (class "Default")
      (node (ref "JP11") (pin "8") (pinfunction "8_8") (pintype "passive"))
      (node (ref "L1") (pin "2") (pinfunction "2_2") (pintype "passive"))
      (node (ref "VIN") (pin "2") (pinfunction "2_2") (pintype "passive"))
      (node (ref "X1") (pin "2") (pinfunction "2_2") (pintype "power_in"))
    )
    (net (code "94") (name "/VIN2_GND") (class "Default")
      (node (ref "VIN") (pin "1") (pinfunction "1_1") (pintype "passive"))
      (node (ref "X1") (pin "1") (pinfunction "1_1") (pintype "power_in"))
    )
    (net (code "95") (name "/VUSB") (class "Default")
      (node (ref "Q4") (pin "3") (pinfunction "D_3") (pintype "passive"))
      (node (ref "TEENSY-3.1/3.2") (pin "VUSB") (pinfunction "VUSB_VUSB") (pintype "power_in"))
    )
    (net (code "96") (name "GND") (class "Default")
      (node (ref "C1") (pin "-") (pinfunction "-_-") (pintype "passive"))
      (node (ref "C2") (pin "1") (pinfunction "P$1_1") (pintype "passive"))
      (node (ref "C3") (pin "1") (pinfunction "P$1_1") (pintype "passive"))
      (node (ref "C4") (pin "1") (pinfunction "P$1_1") (pintype "passive"))
      (node (ref "C5") (pin "1") (pinfunction "P$1_1") (pintype "passive"))
      (node (ref "C6") (pin "-") (pinfunction "-_-") (pintype "passive"))
      (node (ref "C7") (pin "1") (pinfunction "1_1") (pintype "passive"))
      (node (ref "C8") (pin "-") (pinfunction "-_-") (pintype "passive"))
      (node (ref "CR2032") (pin "NEGATIVE") (pinfunction "-_NEGATIVE") (pintype "power_in"))
      (node (ref "D13") (pin "C") (pinfunction "C_C") (pintype "passive"))
      (node (ref "ESP-PGM") (pin "4") (pinfunction "4_4") (pintype "passive"))
      (node (ref "ESP-RST") (pin "2") (pinfunction "2_2") (pintype "passive"))
      (node (ref "HC-05/06/BT12") (pin "4") (pinfunction "4_4") (pintype "passive"))
      (node (ref "IC1") (pin "1") (pinfunction "GND_1") (pintype "power_in"))
      (node (ref "IC2") (pin "1") (pinfunction "GND_1") (pintype "power_in"))
      (node (ref "JP11") (pin "6") (pinfunction "6_6") (pintype "passive"))
      (node (ref "JP11") (pin "7") (pinfunction "7_7") (pintype "passive"))
      (node (ref "JP4") (pin "7") (pinfunction "7_7") (pintype "passive"))
      (node (ref "JP8") (pin "24") (pinfunction "24_24") (pintype "passive"))
      (node (ref "JP8") (pin "25") (pinfunction "25_25") (pintype "passive"))
      (node (ref "JP8") (pin "35") (pinfunction "35_35") (pintype "passive"))
      (node (ref "JP8") (pin "36") (pinfunction "36_36") (pintype "passive"))
      (node (ref "LED10") (pin "C") (pinfunction "C_C") (pintype "passive"))
      (node (ref "MDL1") (pin "9") (pinfunction "GND_9") (pintype "bidirectional"))
      (node (ref "PWR") (pin "C") (pinfunction "C_C") (pintype "passive"))
      (node (ref "Q4") (pin "1") (pinfunction "G_1") (pintype "passive"))
      (node (ref "RESET") (pin "2") (pinfunction "2_2") (pintype "passive"))
      (node (ref "RN4") (pin "3") (pinfunction "2_3") (pintype "passive"))
      (node (ref "SJ1") (pin "1") (pinfunction "1_1") (pintype "passive"))
      (node (ref "SJ2") (pin "1") (pinfunction "1_1") (pintype "passive"))
      (node (ref "SJ3") (pin "1") (pinfunction "1_1") (pintype "passive"))
      (node (ref "SPI") (pin "6") (pinfunction "6_6") (pintype "passive"))
      (node (ref "TEENSY-3.1/3.2") (pin "AGND") (pinfunction "AGND_AGND") (pintype "power_in"))
      (node (ref "TEENSY-3.1/3.2") (pin "GND") (pinfunction "GND_GND") (pintype "power_in"))
      (node (ref "TEENSY-3.1/3.2") (pin "GND1") (pinfunction "GND_GND1") (pintype "power_in"))
      (node (ref "TEENSY-3.1/3.2") (pin "GND2") (pinfunction "GND_GND2") (pintype "power_in"))
      (node (ref "X1") (pin "3") (pinfunction "3_3") (pintype "power_in"))
    )
    (net (code "97") (name "Net-(D1-A)") (class "Default")
      (node (ref "D1") (pin "P$2") (pinfunction "A_P$2") (pintype "bidirectional"))
      (node (ref "L1") (pin "1") (pinfunction "1_1") (pintype "passive"))
    )
    (net (code "98") (name "Net-(D13-PadA)") (class "Default")
      (node (ref "D13") (pin "A") (pinfunction "A_A") (pintype "passive"))
      (node (ref "RN1") (pin "1") (pinfunction "1_1") (pintype "passive"))
    )
    (net (code "99") (name "Net-(HC-PGM-Pad2)") (class "Default")
      (node (ref "HC-PGM") (pin "2") (pinfunction "2_2") (pintype "passive"))
      (node (ref "R2") (pin "1") (pinfunction "1_1") (pintype "passive"))
    )
    (net (code "100") (name "Net-(RN1D-2)") (class "Default")
      (node (ref "PWR") (pin "A") (pinfunction "A_A") (pintype "passive"))
      (node (ref "RN1") (pin "5") (pinfunction "2_5") (pintype "passive"))
    )
    (net (code "101") (name "Net-(RN6B-1)") (class "Default")
      (node (ref "RN6") (pin "1") (pinfunction "1_1") (pintype "passive"))
      (node (ref "RN6") (pin "2") (pinfunction "1_2") (pintype "passive"))
      (node (ref "RN6") (pin "3") (pinfunction "1_3") (pintype "passive"))
      (node (ref "RN6") (pin "4") (pinfunction "1_4") (pintype "passive"))
      (node (ref "SJ5") (pin "1") (pinfunction "1_1") (pintype "passive"))
    )
    (net (code "102") (name "unconnected-(ESP-PGM-Pad1)") (class "Default")
      (node (ref "ESP-PGM") (pin "1") (pinfunction "1_1") (pintype "passive"))
    )
    (net (code "103") (name "unconnected-(ESP-PGM-Pad3)") (class "Default")
      (node (ref "ESP-PGM") (pin "3") (pinfunction "3_3") (pintype "passive"))
    )
    (net (code "104") (name "unconnected-(ESP-RST-Pad1)") (class "Default")
      (node (ref "ESP-RST") (pin "1") (pinfunction "1_1") (pintype "passive"))
    )
    (net (code "105") (name "unconnected-(ESP-RST-Pad3)") (class "Default")
      (node (ref "ESP-RST") (pin "3") (pinfunction "3_3") (pintype "passive"))
    )
    (net (code "106") (name "unconnected-(HC-PGM-Pad1)") (class "Default")
      (node (ref "HC-PGM") (pin "1") (pinfunction "1_1") (pintype "passive"))
    )
    (net (code "107") (name "unconnected-(HC-PGM-Pad3)") (class "Default")
      (node (ref "HC-PGM") (pin "3") (pinfunction "3_3") (pintype "passive"))
    )
    (net (code "108") (name "unconnected-(JP8-Pad33)") (class "Default")
      (node (ref "JP8") (pin "33") (pinfunction "33_33") (pintype "passive"))
    )
    (net (code "109") (name "unconnected-(JP8-Pad34)") (class "Default")
      (node (ref "JP8") (pin "34") (pinfunction "34_34") (pintype "passive"))
    )
    (net (code "110") (name "unconnected-(JP11-Pad1)") (class "Default")
      (node (ref "JP11") (pin "1") (pinfunction "1_1") (pintype "passive"))
    )
    (net (code "111") (name "unconnected-(RESET-Pad1)") (class "Default")
      (node (ref "RESET") (pin "1") (pinfunction "1_1") (pintype "passive"))
    )
    (net (code "112") (name "unconnected-(RESET-Pad4)") (class "Default")
      (node (ref "RESET") (pin "4") (pinfunction "4_4") (pintype "passive"))
    )
  )
)
